# Autoprog.net
KiCad netlist of a schematic drawn in Altium Designer
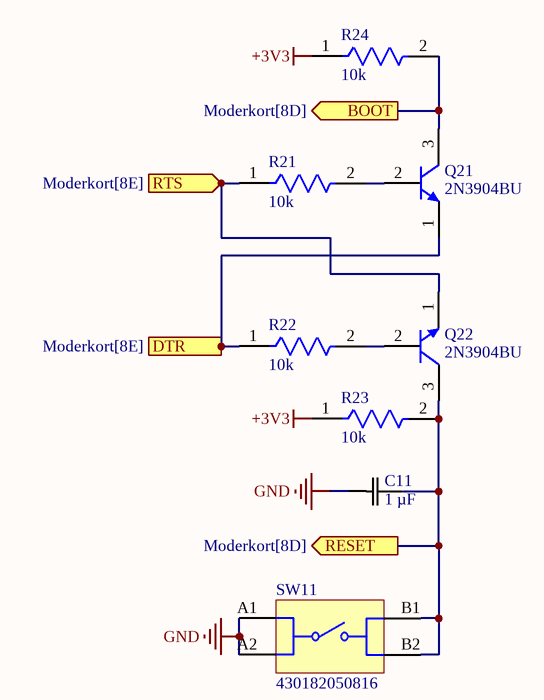
[diagram p0: Autoprog.SchDoc]

(export (version "E")
  (design (tool "Eeschema 10.0.6"))
  (components
    (comp (ref "C11")
      (value "1 µF")
      (footprint "1 µF")
      (description "SMD Auto X7R Flex, Ceramic, 1 uF, 20%, 25 VDC, X7R, SMD, MLCC, FT-CAP, Automotive Grade, 1206")
      (fields
        (field (name "DESIGN ITEM ID") "1 µF")
        (field (name "MANUFACTURER_PART_NUMBER") "C1206X105M3RACAUTO")
        (field (name "COPYRIGHT") "Copyright (C) 2025 Ultra Librarian. All rights reserved.")
      )
      (libsource (lib "Linköpings Universitet (SE)") (part "1 µF"))
    )
    (comp (ref "Q21")
      (value "2N3904BU")
      (footprint "FAIR-TO-92")
      (description "NPN General-Purpose Amplifier, 40 V VCEO, 0.2 A, -55 to 150 degC, 2-Pin TO-92, RoHS, Bulk")
      (fields (field (name "MANUFACTURER") "FairchildSemiconductor"))
      (libsource (lib "Altium Content Vault") (part "NPN-E1B2C3-3"))
    )
    (comp (ref "Q22")
      (value "2N3904BU")
      (footprint "FAIR-TO-92")
      (description "NPN General-Purpose Amplifier, 40 V VCEO, 0.2 A, -55 to 150 degC, 2-Pin TO-92, RoHS, Bulk")
      (fields (field (name "MANUFACTURER") "FairchildSemiconductor"))
      (libsource (lib "Altium Content Vault") (part "NPN-E1B2C3-3"))
    )
    (comp (ref "R21")
      (value "10k")
      (footprint "FP-RT1206-IPC_C")
      (description "Fixed Resistor, Thin Film, 0.25W, 470ohm, 200V, 0.1% +/-Tol, 25ppm/Cel, Surface Mount, 1206")
      (fields (field (name "POWER") "250mW") (field (name "TOLERANCE") "0.1%"))
      (libsource (lib "Linköpings Universitet (SE)") (part "1029c3af85768c4190bb7ad29bc67b5"))
    )
    (comp (ref "R22")
      (value "10k")
      (footprint "FP-RT1206-IPC_C")
      (description "Fixed Resistor, Thin Film, 0.25W, 470ohm, 200V, 0.1% +/-Tol, 25ppm/Cel, Surface Mount, 1206")
      (fields (field (name "POWER") "250mW") (field (name "TOLERANCE") "0.1%"))
      (libsource (lib "Linköpings Universitet (SE)") (part "1029c3af85768c4190bb7ad29bc67b5"))
    )
    (comp (ref "R23")
      (value "10k")
      (footprint "FP-RT1206-IPC_C")
      (description "Fixed Resistor, Thin Film, 0.25W, 470ohm, 200V, 0.1% +/-Tol, 25ppm/Cel, Surface Mount, 1206")
      (fields (field (name "POWER") "250mW") (field (name "TOLERANCE") "0.1%"))
      (libsource (lib "Linköpings Universitet (SE)") (part "1029c3af85768c4190bb7ad29bc67b5"))
    )
    (comp (ref "R24")
      (value "10k")
      (footprint "FP-RT1206-IPC_C")
      (description "Fixed Resistor, Thin Film, 0.25W, 470ohm, 200V, 0.1% +/-Tol, 25ppm/Cel, Surface Mount, 1206")
      (fields (field (name "POWER") "250mW") (field (name "TOLERANCE") "0.1%"))
      (libsource (lib "Linköpings Universitet (SE)") (part "1029c3af85768c4190bb7ad29bc67b5"))
    )
    (comp (ref "SW11")
      (value "430182050816")
      (footprint "430182050816")
      (description "Switch Tactile N.O. SPST Round Button Gull Wing 0.05A 12VDC 1000000Cycles 1.57N SMD Reel")
      (libsource (lib "Altium Content Vault") (part "SPST-NO_4P"))
    )
  )
  (nets
    (net (code "1") (name "+3V3") (class "Default")
      (node (ref "R23") (pin "1") (pinfunction "1_1") (pintype "passive"))
      (node (ref "R24") (pin "1") (pinfunction "1_1") (pintype "passive"))
    )
    (net (code "2") (name "/BOOT") (class "Default")
      (node (ref "Q21") (pin "3") (pinfunction "C_3") (pintype "passive"))
      (node (ref "R24") (pin "2") (pinfunction "2_2") (pintype "passive"))
    )
    (net (code "3") (name "/DTR") (class "Default")
      (node (ref "Q21") (pin "1") (pinfunction "E_1") (pintype "passive"))
      (node (ref "R22") (pin "1") (pinfunction "1_1") (pintype "passive"))
    )
    (net (code "4") (name "/RESET") (class "Default")
      (node (ref "C11") (pin "2") (pinfunction "2_2") (pintype "passive"))
      (node (ref "Q22") (pin "3") (pinfunction "C_3") (pintype "passive"))
      (node (ref "R23") (pin "2") (pinfunction "2_2") (pintype "passive"))
      (node (ref "SW11") (pin "B1") (pinfunction "B1_B1") (pintype "passive"))
      (node (ref "SW11") (pin "B2") (pinfunction "B2_B2") (pintype "passive"))
    )
    (net (code "5") (name "/RTS") (class "Default")
      (node (ref "Q22") (pin "1") (pinfunction "E_1") (pintype "passive"))
      (node (ref "R21") (pin "1") (pinfunction "1_1") (pintype "passive"))
    )
    (net (code "6") (name "GND") (class "Default")
      (node (ref "C11") (pin "1") (pinfunction "1_1") (pintype "passive"))
      (node (ref "SW11") (pin "A1") (pinfunction "A1_A1") (pintype "passive"))
      (node (ref "SW11") (pin "A2") (pinfunction "A2_A2") (pintype "passive"))
    )
    (net (code "7") (name "Net-(Q21-B)") (class "Default")
      (node (ref "Q21") (pin "2") (pinfunction "B_2") (pintype "passive"))
      (node (ref "R21") (pin "2") (pinfunction "2_2") (pintype "passive"))
    )
    (net (code "8") (name "Net-(Q22-B)") (class "Default")
      (node (ref "Q22") (pin "2") (pinfunction "B_2") (pintype "passive"))
      (node (ref "R22") (pin "2") (pinfunction "2_2") (pintype "passive"))
    )
  )
)
